# 3_3V_Switch_Mode_PSU_5V_disabled.net
KiCad netlist of a schematic drawn in Altium Designer
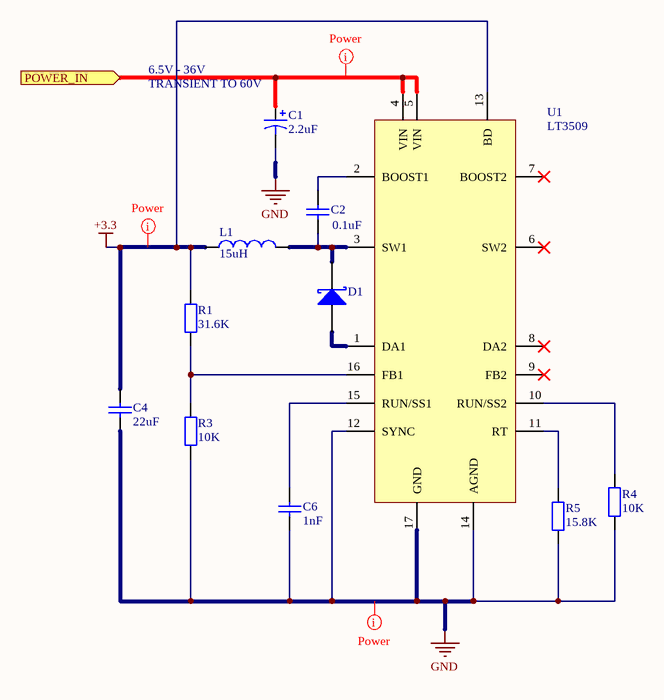
[diagram p0: 3.3V Switch Mode PSU (5V disabled).SchDoc]

(export (version "E")
  (design (tool "Eeschema 10.0.6"))
  (components
    (comp (ref "C1")
      (value "2.2uF")
      (footprint "EEEHC1H2R2R")
      (description "Polarized Capacitor (Radial)")
      (fields (field (name "Comment") "Cap Pol1") (field (name "PUBLISHER") "Altium Limited"))
      (libsource (lib "Miscellaneous Devices") (part "Cap Pol1"))
    )
    (comp (ref "C2")
      (value "0.1uF")
      (footprint "C0603")
      (description "Capacitor")
      (fields (field (name "Comment") "Cap") (field (name "PUBLISHER") "Altium Limited"))
      (libsource (lib "Miscellaneous Devices") (part "Cap"))
    )
    (comp (ref "C4")
      (value "22uF")
      (footprint "C0805")
      (description "Capacitor")
      (fields (field (name "Comment") "Cap"))
      (libsource (lib "Miscellaneous Devices") (part "Cap"))
    )
    (comp (ref "C6")
      (value "1nF")
      (footprint "C0603")
      (description "Capacitor")
      (fields (field (name "Comment") "Cap"))
      (libsource (lib "Miscellaneous Devices") (part "Cap"))
    )
    (comp (ref "D1")
      (value "D Schottky")
      (footprint "VS-10BQ030TRPBF")
      (description "Schottky Diode")
      (fields (field (name "PUBLISHER") "Altium Limited"))
      (libsource (lib "Miscellaneous Devices") (part "D Schottky"))
    )
    (comp (ref "L1")
      (value "15uH")
      (footprint "SDR0604-150YL")
      (description "Inductor")
      (fields (field (name "PUBLISHER") "Altium Limited"))
      (libsource (lib "Miscellaneous Devices") (part "Inductor"))
    )
    (comp (ref "R1")
      (value "31.6K")
      (footprint "R0603")
      (description "Resistor")
      (fields (field (name "Comment") "Res"))
      (libsource (lib "Miscellaneous Devices") (part "Res2"))
    )
    (comp (ref "R3")
      (value "10K")
      (footprint "R0603")
      (description "Resistor")
      (fields (field (name "Comment") "Res"))
      (libsource (lib "Miscellaneous Devices") (part "Res2"))
    )
    (comp (ref "R4")
      (value "10K")
      (footprint "R0603")
      (description "Resistor")
      (fields (field (name "Comment") "Res"))
      (libsource (lib "Miscellaneous Devices") (part "Res2"))
    )
    (comp (ref "R5")
      (value "15.8K")
      (footprint "R0603")
      (description "Resistor")
      (fields (field (name "Comment") "Res"))
      (libsource (lib "Miscellaneous Devices") (part "Res2"))
    )
    (comp (ref "U1") (value "LT3509") (footprint "LT3509") (libsource (lib "LT3509") (part "LT3509")))
  )
  (nets
    (net (code "1") (name "+3.3") (class "Default")
      (node (ref "C4") (pin "1") (pinfunction "1_1") (pintype "passive"))
      (node (ref "L1") (pin "1") (pinfunction "1_1") (pintype "passive"))
      (node (ref "R1") (pin "2") (pinfunction "2_2") (pintype "passive"))
      (node (ref "U1") (pin "13") (pinfunction "BD_13") (pintype "passive"))
    )
    (net (code "2") (name "/POWER_IN") (class "Default")
      (node (ref "C1") (pin "1") (pinfunction "1_1") (pintype "passive"))
      (node (ref "U1") (pin "4") (pinfunction "VIN_4") (pintype "passive"))
      (node (ref "U1") (pin "5") (pinfunction "VIN_5") (pintype "passive"))
    )
    (net (code "3") (name "GND") (class "Default")
      (node (ref "C1") (pin "2") (pinfunction "2_2") (pintype "passive"))
      (node (ref "C4") (pin "2") (pinfunction "2_2") (pintype "passive"))
      (node (ref "C6") (pin "2") (pinfunction "2_2") (pintype "passive"))
      (node (ref "R3") (pin "1") (pinfunction "1_1") (pintype "passive"))
      (node (ref "R4") (pin "1") (pinfunction "1_1") (pintype "passive"))
      (node (ref "R5") (pin "1") (pinfunction "1_1") (pintype "passive"))
      (node (ref "U1") (pin "12") (pinfunction "SYNC_12") (pintype "passive"))
      (node (ref "U1") (pin "14") (pinfunction "AGND_14") (pintype "power_in"))
      (node (ref "U1") (pin "17") (pinfunction "GND_17") (pintype "power_in"))
    )
    (net (code "4") (name "Net-(D1-A)") (class "Default")
      (node (ref "D1") (pin "1") (pinfunction "A_1") (pintype "passive"))
      (node (ref "U1") (pin "1") (pinfunction "DA1_1") (pintype "passive"))
    )
    (net (code "5") (name "Net-(D1-K)") (class "Default")
      (node (ref "C2") (pin "1") (pinfunction "1_1") (pintype "passive"))
      (node (ref "D1") (pin "2") (pinfunction "K_2") (pintype "passive"))
      (node (ref "L1") (pin "2") (pinfunction "2_2") (pintype "passive"))
      (node (ref "U1") (pin "3") (pinfunction "SW1_3") (pintype "passive"))
    )
    (net (code "6") (name "Net-(U1-BOOST1)") (class "Default")
      (node (ref "C2") (pin "2") (pinfunction "2_2") (pintype "passive"))
      (node (ref "U1") (pin "2") (pinfunction "BOOST1_2") (pintype "passive"))
    )
    (net (code "7") (name "Net-(U1-FB1)") (class "Default")
      (node (ref "R1") (pin "1") (pinfunction "1_1") (pintype "passive"))
      (node (ref "R3") (pin "2") (pinfunction "2_2") (pintype "passive"))
      (node (ref "U1") (pin "16") (pinfunction "FB1_16") (pintype "passive"))
    )
    (net (code "8") (name "Net-(U1-RT)") (class "Default")
      (node (ref "R5") (pin "2") (pinfunction "2_2") (pintype "passive"))
      (node (ref "U1") (pin "11") (pinfunction "RT_11") (pintype "passive"))
    )
    (net (code "9") (name "Net-(U1-RUN{slash}SS1)") (class "Default")
      (node (ref "C6") (pin "1") (pinfunction "1_1") (pintype "passive"))
      (node (ref "U1") (pin "15") (pinfunction "RUN/SS1_15") (pintype "passive"))
    )
    (net (code "10") (name "Net-(U1-RUN{slash}SS2)") (class "Default")
      (node (ref "R4") (pin "2") (pinfunction "2_2") (pintype "passive"))
      (node (ref "U1") (pin "10") (pinfunction "RUN/SS2_10") (pintype "passive"))
    )
    (net (code "11") (name "unconnected-(U1-BOOST2-Pad7)") (class "Default")
      (node (ref "U1") (pin "7") (pinfunction "BOOST2_7") (pintype "passive+no_connect"))
    )
    (net (code "12") (name "unconnected-(U1-DA2-Pad8)") (class "Default")
      (node (ref "U1") (pin "8") (pinfunction "DA2_8") (pintype "passive+no_connect"))
    )
    (net (code "13") (name "unconnected-(U1-FB2-Pad9)") (class "Default")
      (node (ref "U1") (pin "9") (pinfunction "FB2_9") (pintype "passive+no_connect"))
    )
    (net (code "14") (name "unconnected-(U1-SW2-Pad6)") (class "Default")
      (node (ref "U1") (pin "6") (pinfunction "SW2_6") (pintype "passive+no_connect"))
    )
  )
)
